# Main.net
KiCad netlist of a schematic drawn in Altium Designer
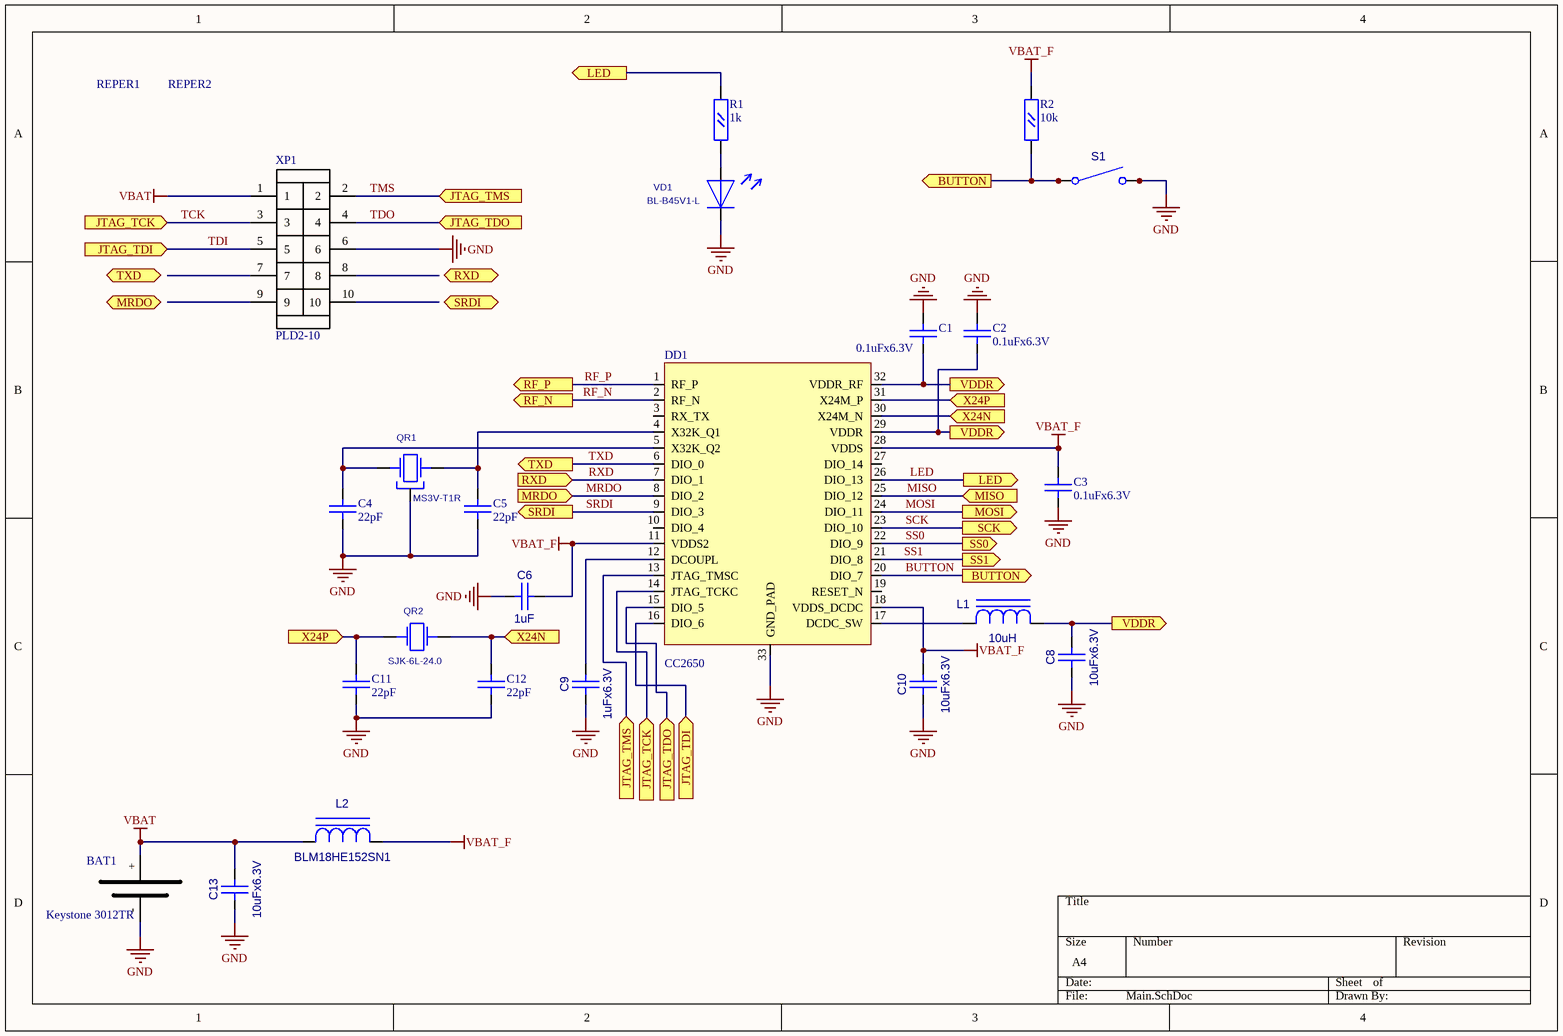
[diagram p0: Main.SchDoc]

(export (version "E")
  (design (tool "Eeschema 10.0.6"))
  (components
    (comp (ref "BAT1")
      (value "Keystone 3012TR")
      (footprint "BAT_1632")
      (libsource (lib "gprs_modem_2") (part "BAT_1632"))
    )
    (comp (ref "C1")
      (value "0.1uFx6.3V")
      (footprint "CC0402")
      (libsource (lib "gprs_modem_2") (part "CC0402"))
    )
    (comp (ref "C2")
      (value "0.1uFx6.3V")
      (footprint "CC0402")
      (libsource (lib "gprs_modem_2") (part "CC0402"))
    )
    (comp (ref "C3")
      (value "0.1uFx6.3V")
      (footprint "CC0402")
      (libsource (lib "gprs_modem_2") (part "CC0402"))
    )
    (comp (ref "C4") (value "22pF") (footprint "CC0402") (libsource (lib "gprs_modem_2") (part "CC0402")))
    (comp (ref "C5") (value "22pF") (footprint "CC0402") (libsource (lib "gprs_modem_2") (part "CC0402")))
    (comp (ref "C6")
      (value "1uF")
      (footprint "CC0603")
      (description "CC0603")
      (libsource (lib "gprs_modem_2") (part "CC0603"))
    )
    (comp (ref "C8")
      (value "10uFx6.3V")
      (footprint "CC0603")
      (description "CC0603")
      (libsource (lib "gprs_modem_2") (part "CC0603"))
    )
    (comp (ref "C9")
      (value "1uFx6.3V")
      (footprint "CC0603")
      (description "CC0603")
      (libsource (lib "gprs_modem_2") (part "CC0603"))
    )
    (comp (ref "C10")
      (value "10uFx6.3V")
      (footprint "CC0603")
      (description "CC0603")
      (libsource (lib "gprs_modem_2") (part "CC0603"))
    )
    (comp (ref "C11") (value "22pF") (footprint "CC0402") (libsource (lib "gprs_modem_2") (part "CC0402")))
    (comp (ref "C12") (value "22pF") (footprint "CC0402") (libsource (lib "gprs_modem_2") (part "CC0402")))
    (comp (ref "C13")
      (value "10uFx6.3V")
      (footprint "CC0603")
      (description "CC0603")
      (libsource (lib "gprs_modem_2") (part "CC0603"))
    )
    (comp (ref "DD1")
      (value "CC2650")
      (footprint "QFN32_TI")
      (description "CC2650RHBT")
      (libsource (lib "gprs_modem_2") (part "CC2650RHB"))
    )
    (comp (ref "L1")
      (value "10uH")
      (footprint "L0603")
      (description "L0603")
      (libsource (lib "gprs_modem_2") (part "L0603"))
    )
    (comp (ref "L2")
      (value "BLM18HE152SN1")
      (footprint "L0603")
      (description "L0603")
      (libsource (lib "gprs_modem_2") (part "L0603"))
    )
    (comp (ref "QR1")
      (value "MS3V-T1R")
      (footprint "MS3V-T1R")
      (description "CRYSTAL_32768 Hz")
      (libsource (lib "gprs_modem_2") (part "MS3V-T1R"))
    )
    (comp (ref "QR2")
      (value "SJK-6L-24.0")
      (footprint "AC5032_2")
      (description "AC5032/2")
      (libsource (lib "gprs_modem_2") (part "AC5032_2"))
    )
    (comp (ref "R1") (value "1k") (footprint "RC0402") (libsource (lib "gprs_modem_2") (part "RC0402")))
    (comp (ref "R2") (value "10k") (footprint "RC0402") (libsource (lib "gprs_modem_2") (part "RC0402")))
    (comp (ref "REPER1")
      (value "REPER1.2")
      (footprint "REPER1.2")
      (libsource (lib "gprs_modem_2") (part "REPER1.2"))
    )
    (comp (ref "REPER2")
      (value "REPER1.2")
      (footprint "REPER1.2")
      (libsource (lib "gprs_modem_2") (part "REPER1.2"))
    )
    (comp (ref "S1")
      (value "DTSM-61N")
      (footprint "DTSM-61N")
      (description "Switch, Single Pole, Single Throw, Normally Open")
      (libsource (lib "gprs_modem_2") (part "DTSM-61N"))
    )
    (comp (ref "VD1")
      (value "BL-B45V1-L")
      (footprint "LED3")
      (description "LED_3")
      (libsource (lib "gprs_modem_2") (part "LED_3"))
    )
    (comp (ref "XP1")
      (value "PLD2-10")
      (footprint "PLD2-10")
      (libsource (lib "gprs_modem_2") (part "PLD2-10"))
    )
  )
  (nets
    (net (code "1") (name "/BUTTON") (class "Default")
      (node (ref "DD1") (pin "20") (pinfunction "DIO_7_20") (pintype "passive"))
      (node (ref "R2") (pin "1") (pinfunction "A_1") (pintype "passive"))
      (node (ref "S1") (pin "1") (pinfunction "C1_1") (pintype "passive"))
      (node (ref "S1") (pin "2") (pintype "passive"))
    )
    (net (code "2") (name "/LED") (class "Default")
      (node (ref "DD1") (pin "26") (pinfunction "DIO_13_26") (pintype "passive"))
      (node (ref "R1") (pin "2") (pinfunction "B_2") (pintype "passive"))
    )
    (net (code "3") (name "/MISO") (class "Default")
      (node (ref "DD1") (pin "25") (pinfunction "DIO_12_25") (pintype "passive"))
    )
    (net (code "4") (name "/MOSI") (class "Default")
      (node (ref "DD1") (pin "24") (pinfunction "DIO_11_24") (pintype "passive"))
    )
    (net (code "5") (name "/MRDO") (class "Default")
      (node (ref "DD1") (pin "8") (pinfunction "DIO_2_8") (pintype "passive"))
    )
    (net (code "6") (name "/RF_N") (class "Default")
      (node (ref "DD1") (pin "2") (pinfunction "RF_N_2") (pintype "passive"))
    )
    (net (code "7") (name "/RF_P") (class "Default")
      (node (ref "DD1") (pin "1") (pinfunction "RF_P_1") (pintype "passive"))
    )
    (net (code "8") (name "/RXD") (class "Default")
      (node (ref "DD1") (pin "7") (pinfunction "DIO_1_7") (pintype "passive"))
    )
    (net (code "9") (name "/SCK") (class "Default")
      (node (ref "DD1") (pin "23") (pinfunction "DIO_10_23") (pintype "passive"))
    )
    (net (code "10") (name "/SRDI") (class "Default")
      (node (ref "DD1") (pin "9") (pinfunction "DIO_3_9") (pintype "passive"))
    )
    (net (code "11") (name "/SS0") (class "Default")
      (node (ref "DD1") (pin "22") (pinfunction "DIO_9_22") (pintype "passive"))
    )
    (net (code "12") (name "/SS1") (class "Default")
      (node (ref "DD1") (pin "21") (pinfunction "DIO_8_21") (pintype "passive"))
    )
    (net (code "13") (name "/TCK") (class "Default")
      (node (ref "DD1") (pin "14") (pinfunction "JTAG_TCKC_14") (pintype "passive"))
      (node (ref "XP1") (pin "3") (pinfunction "3_3") (pintype "passive"))
    )
    (net (code "14") (name "/TDI") (class "Default")
      (node (ref "DD1") (pin "16") (pinfunction "DIO_6_16") (pintype "passive"))
      (node (ref "XP1") (pin "5") (pinfunction "5_5") (pintype "passive"))
    )
    (net (code "15") (name "/TDO") (class "Default")
      (node (ref "DD1") (pin "15") (pinfunction "DIO_5_15") (pintype "passive"))
      (node (ref "XP1") (pin "4") (pinfunction "4_4") (pintype "passive"))
    )
    (net (code "16") (name "/TMS") (class "Default")
      (node (ref "DD1") (pin "13") (pinfunction "JTAG_TMSC_13") (pintype "passive"))
      (node (ref "XP1") (pin "2") (pinfunction "2_2") (pintype "passive"))
    )
    (net (code "17") (name "/TXD") (class "Default")
      (node (ref "DD1") (pin "6") (pinfunction "DIO_0_6") (pintype "passive"))
    )
    (net (code "18") (name "/VDDR") (class "Default")
      (node (ref "C1") (pin "1") (pinfunction "A_1") (pintype "passive"))
      (node (ref "C2") (pin "1") (pinfunction "A_1") (pintype "passive"))
      (node (ref "C8") (pin "2") (pinfunction "B_2") (pintype "passive"))
      (node (ref "DD1") (pin "29") (pinfunction "VDDR_29") (pintype "passive"))
      (node (ref "DD1") (pin "32") (pinfunction "VDDR_RF_32") (pintype "passive"))
      (node (ref "L1") (pin "2") (pinfunction "C_2") (pintype "passive"))
    )
    (net (code "19") (name "/X24N") (class "Default")
      (node (ref "C12") (pin "2") (pinfunction "B_2") (pintype "passive"))
      (node (ref "DD1") (pin "30") (pinfunction "X24M_N_30") (pintype "passive"))
      (node (ref "QR2") (pin "2") (pintype "passive"))
    )
    (net (code "20") (name "/X24P") (class "Default")
      (node (ref "C11") (pin "2") (pinfunction "B_2") (pintype "passive"))
      (node (ref "DD1") (pin "31") (pinfunction "X24M_P_31") (pintype "passive"))
      (node (ref "QR2") (pin "1") (pintype "passive"))
    )
    (net (code "21") (name "GND") (class "Default")
      (node (ref "BAT1") (pin "-") (pinfunction "-_-") (pintype "passive"))
      (node (ref "C1") (pin "2") (pinfunction "B_2") (pintype "passive"))
      (node (ref "C10") (pin "1") (pinfunction "A_1") (pintype "passive"))
      (node (ref "C11") (pin "1") (pinfunction "A_1") (pintype "passive"))
      (node (ref "C12") (pin "1") (pinfunction "A_1") (pintype "passive"))
      (node (ref "C13") (pin "1") (pinfunction "A_1") (pintype "passive"))
      (node (ref "C2") (pin "2") (pinfunction "B_2") (pintype "passive"))
      (node (ref "C3") (pin "1") (pinfunction "A_1") (pintype "passive"))
      (node (ref "C4") (pin "1") (pinfunction "A_1") (pintype "passive"))
      (node (ref "C5") (pin "1") (pinfunction "A_1") (pintype "passive"))
      (node (ref "C6") (pin "1") (pinfunction "A_1") (pintype "passive"))
      (node (ref "C8") (pin "1") (pinfunction "A_1") (pintype "passive"))
      (node (ref "C9") (pin "1") (pinfunction "A_1") (pintype "passive"))
      (node (ref "DD1") (pin "33") (pinfunction "GND_PAD_33") (pintype "passive"))
      (node (ref "QR1") (pin "3") (pinfunction "3_3") (pintype "passive"))
      (node (ref "S1") (pin "3") (pinfunction "C2_3") (pintype "passive"))
      (node (ref "S1") (pin "4") (pintype "passive"))
      (node (ref "VD1") (pin "1") (pintype "passive"))
      (node (ref "XP1") (pin "6") (pinfunction "6_6") (pintype "passive"))
    )
    (net (code "22") (name "Net-(C4-B)") (class "Default")
      (node (ref "C4") (pin "2") (pinfunction "B_2") (pintype "passive"))
      (node (ref "DD1") (pin "5") (pinfunction "X32K_Q2_5") (pintype "passive"))
      (node (ref "QR1") (pin "2") (pinfunction "X2_2") (pintype "passive"))
    )
    (net (code "23") (name "Net-(C5-B)") (class "Default")
      (node (ref "C5") (pin "2") (pinfunction "B_2") (pintype "passive"))
      (node (ref "DD1") (pin "4") (pinfunction "X32K_Q1_4") (pintype "passive"))
      (node (ref "QR1") (pin "1") (pinfunction "X1_1") (pintype "passive"))
    )
    (net (code "24") (name "Net-(C9-B)") (class "Default")
      (node (ref "C9") (pin "2") (pinfunction "B_2") (pintype "passive"))
      (node (ref "DD1") (pin "12") (pinfunction "DCOUPL_12") (pintype "passive"))
    )
    (net (code "25") (name "Net-(DD1-DCDC_SW)") (class "Default")
      (node (ref "DD1") (pin "17") (pinfunction "DCDC_SW_17") (pintype "passive"))
      (node (ref "L1") (pin "1") (pinfunction "A_1") (pintype "passive"))
    )
    (net (code "26") (name "Net-(R1-A)") (class "Default")
      (node (ref "R1") (pin "1") (pinfunction "A_1") (pintype "passive"))
      (node (ref "VD1") (pin "2") (pintype "passive"))
    )
    (net (code "27") (name "VBAT") (class "Default")
      (node (ref "BAT1") (pin "+") (pinfunction "+_+") (pintype "passive"))
      (node (ref "C13") (pin "2") (pinfunction "B_2") (pintype "passive"))
      (node (ref "L2") (pin "1") (pinfunction "A_1") (pintype "passive"))
      (node (ref "XP1") (pin "1") (pinfunction "1_1") (pintype "passive"))
    )
    (net (code "28") (name "VBAT_F") (class "Default")
      (node (ref "C10") (pin "2") (pinfunction "B_2") (pintype "passive"))
      (node (ref "C3") (pin "2") (pinfunction "B_2") (pintype "passive"))
      (node (ref "C6") (pin "2") (pinfunction "B_2") (pintype "passive"))
      (node (ref "DD1") (pin "11") (pinfunction "VDDS2_11") (pintype "passive"))
      (node (ref "DD1") (pin "18") (pinfunction "VDDS_DCDC_18") (pintype "passive"))
      (node (ref "DD1") (pin "28") (pinfunction "VDDS_28") (pintype "passive"))
      (node (ref "L2") (pin "2") (pinfunction "C_2") (pintype "passive"))
      (node (ref "R2") (pin "2") (pinfunction "B_2") (pintype "passive"))
    )
    (net (code "29") (name "unconnected-(DD1-DIO_4-Pad10)") (class "Default")
      (node (ref "DD1") (pin "10") (pinfunction "DIO_4_10") (pintype "passive"))
    )
    (net (code "30") (name "unconnected-(DD1-DIO_14-Pad27)") (class "Default")
      (node (ref "DD1") (pin "27") (pinfunction "DIO_14_27") (pintype "passive"))
    )
    (net (code "31") (name "unconnected-(DD1-RESET_N-Pad19)") (class "Default")
      (node (ref "DD1") (pin "19") (pinfunction "RESET_N_19") (pintype "passive"))
    )
    (net (code "32") (name "unconnected-(DD1-RX_TX-Pad3)") (class "Default")
      (node (ref "DD1") (pin "3") (pinfunction "RX_TX_3") (pintype "passive"))
    )
    (net (code "33") (name "unconnected-(REPER1-Pad1)") (class "Default")
      (node (ref "REPER1") (pin "1") (pintype "passive"))
    )
    (net (code "34") (name "unconnected-(REPER2-Pad1)") (class "Default")
      (node (ref "REPER2") (pin "1") (pintype "passive"))
    )
    (net (code "35") (name "unconnected-(XP1-Pad7)") (class "Default")
      (node (ref "XP1") (pin "7") (pinfunction "7_7") (pintype "passive"))
    )
    (net (code "36") (name "unconnected-(XP1-Pad8)") (class "Default")
      (node (ref "XP1") (pin "8") (pinfunction "8_8") (pintype "passive"))
    )
    (net (code "37") (name "unconnected-(XP1-Pad9)") (class "Default")
      (node (ref "XP1") (pin "9") (pinfunction "9_9") (pintype "passive"))
    )
    (net (code "38") (name "unconnected-(XP1-Pad10)") (class "Default")
      (node (ref "XP1") (pin "10") (pinfunction "10_10") (pintype "passive"))
    )
  )
)
